# 48V_Rail.net
KiCad netlist of a schematic drawn in Altium Designer
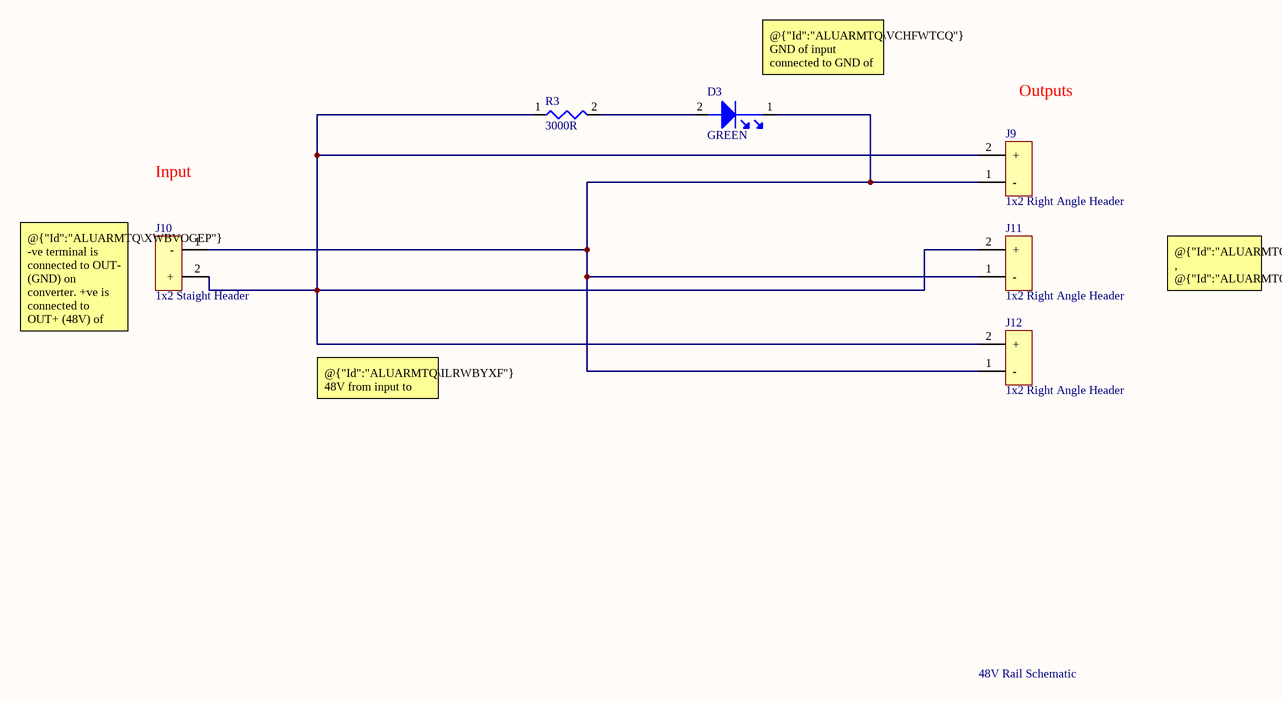
[diagram p0: 48V Rail.SchDoc]

(export (version "E")
  (design (tool "Eeschema 10.0.6"))
  (components
    (comp (ref "D3")
      (value "GREEN")
      (footprint "LED")
      (description "Green T-1 3/4 5 mm 20° Tinted 80 mcd 2.2 V Solid State LED Lamp Through Hole")
      (fields (field (name "MANUFACTURER") "Kingbright") (field (name "MANUFACTURER PART NUMBER") "WP7113GT"))
      (libsource (lib "VR Interface SchLib") (part "WP7113GT"))
    )
    (comp (ref "J9")
      (value "1x2 Right Angle Header")
      (footprint "39291028 Molex Output")
      (description "Connector Wire to Board Header 2 Position 4.2mm Solder Right Angle Thru-Hole Tray")
      (fields (field (name "MANUFACTURER") "Molex") (field (name "MANUFACTURER PART NUMBER") "39-29-1028"))
      (libsource (lib "VR Interface SchLib") (part "39-29-1028"))
    )
    (comp (ref "J10")
      (value "1x2 Staight Header")
      (footprint "39281023 Molex Input")
      (description "Connector Wire to Board Header 2 Position 4.2mm Solder Straight Thru-Hole Tray")
      (fields (field (name "MANUFACTURER") "Molex") (field (name "MANUFACTURER PART NUMBER") "39-28-1023"))
      (libsource (lib "VR Interface SchLib") (part "39-28-1023"))
    )
    (comp (ref "J11")
      (value "1x2 Right Angle Header")
      (footprint "39291028 Molex Output")
      (description "Connector Wire to Board Header 2 Position 4.2mm Solder Right Angle Thru-Hole Tray")
      (fields (field (name "MANUFACTURER") "Molex") (field (name "MANUFACTURER PART NUMBER") "39-29-1028"))
      (libsource (lib "VR Interface SchLib") (part "39-29-1028"))
    )
    (comp (ref "J12")
      (value "1x2 Right Angle Header")
      (footprint "39291028 Molex Output")
      (description "Connector Wire to Board Header 2 Position 4.2mm Solder Right Angle Thru-Hole Tray")
      (fields (field (name "MANUFACTURER") "Molex") (field (name "MANUFACTURER PART NUMBER") "39-29-1028"))
      (libsource (lib "VR Interface SchLib") (part "39-29-1028"))
    )
    (comp (ref "R3")
      (value "3000R")
      (footprint "3000R")
      (description "General Type Carbon Film Resistor 3kOhm 1/4W 5% Axial Bulk")
      (fields
        (field (name "MANUFACTURER") "Yageo")
        (field (name "MANUFACTURER PART NUMBER") "CFR-25JB-52-3K")
      )
      (libsource (lib "VR Interface SchLib") (part "CFR-25JB-52-3K"))
    )
  )
  (nets
    (net (code "1") (name "Net-(D3-Pad2)") (class "Default")
      (node (ref "D3") (pin "2") (pinfunction "2_2") (pintype "passive"))
      (node (ref "R3") (pin "2") (pinfunction "2_2") (pintype "passive"))
    )
    (net (code "2") (name "Net-(J10-+)") (class "Default")
      (node (ref "J10") (pin "2") (pinfunction "+_2") (pintype "passive"))
      (node (ref "J11") (pin "2") (pinfunction "+_2") (pintype "passive"))
      (node (ref "J12") (pin "2") (pinfunction "+_2") (pintype "passive"))
      (node (ref "J9") (pin "2") (pinfunction "+_2") (pintype "passive"))
      (node (ref "R3") (pin "1") (pinfunction "1_1") (pintype "passive"))
    )
    (net (code "3") (name "Net-(J10--)") (class "Default")
      (node (ref "D3") (pin "1") (pinfunction "1_1") (pintype "passive"))
      (node (ref "J10") (pin "1") (pinfunction "-_1") (pintype "passive"))
      (node (ref "J11") (pin "1") (pinfunction "-_1") (pintype "passive"))
      (node (ref "J12") (pin "1") (pinfunction "-_1") (pintype "passive"))
      (node (ref "J9") (pin "1") (pinfunction "-_1") (pintype "passive"))
    )
  )
)
